# P2P_1.net
KiCad netlist of a schematic drawn in EAGLE
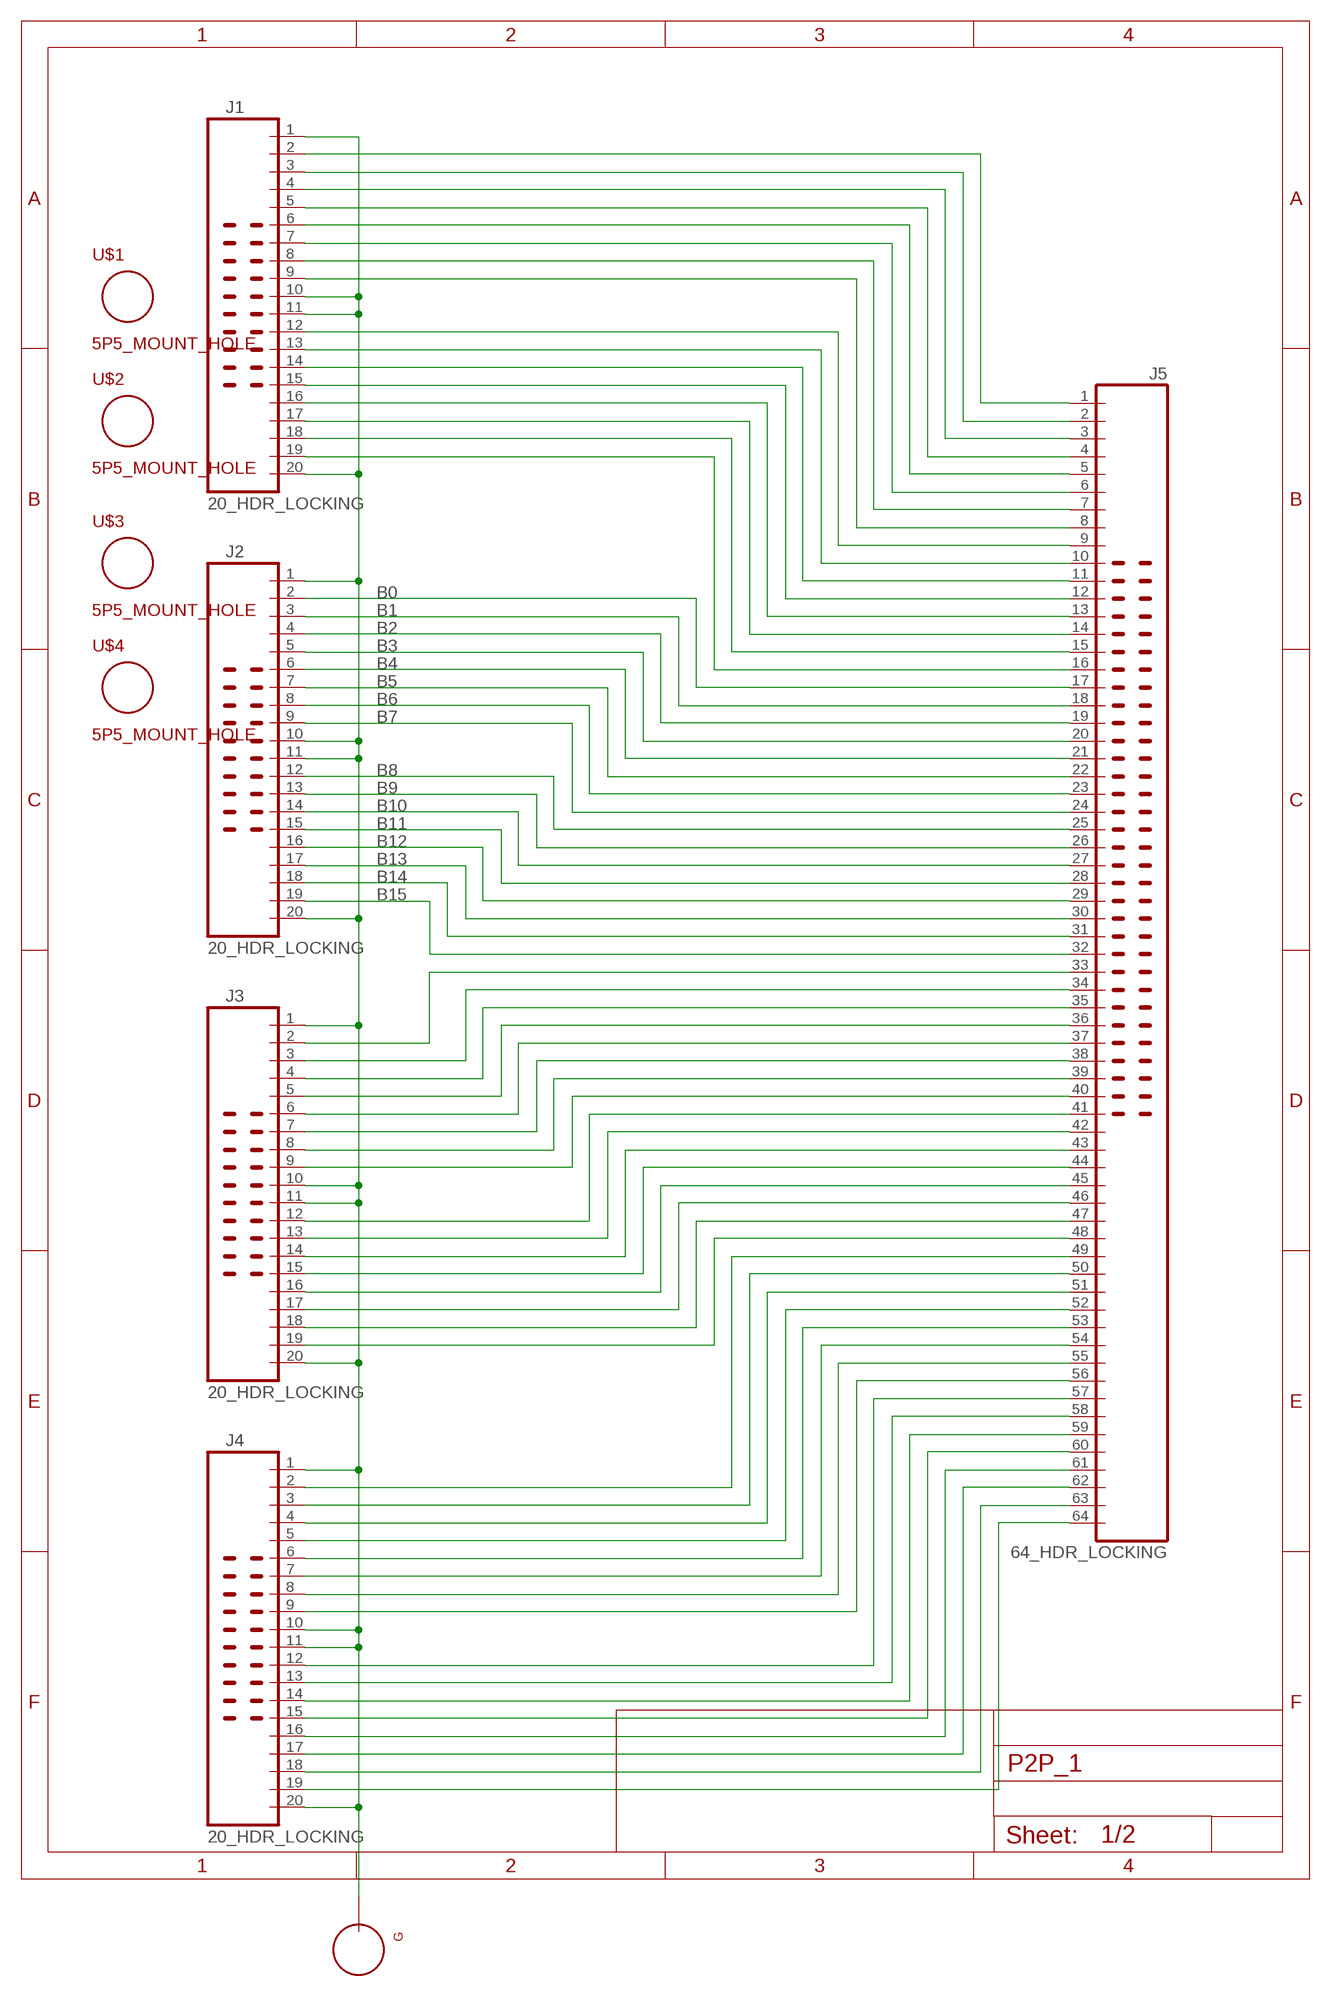
[diagram p0: schematic, sheet 1]
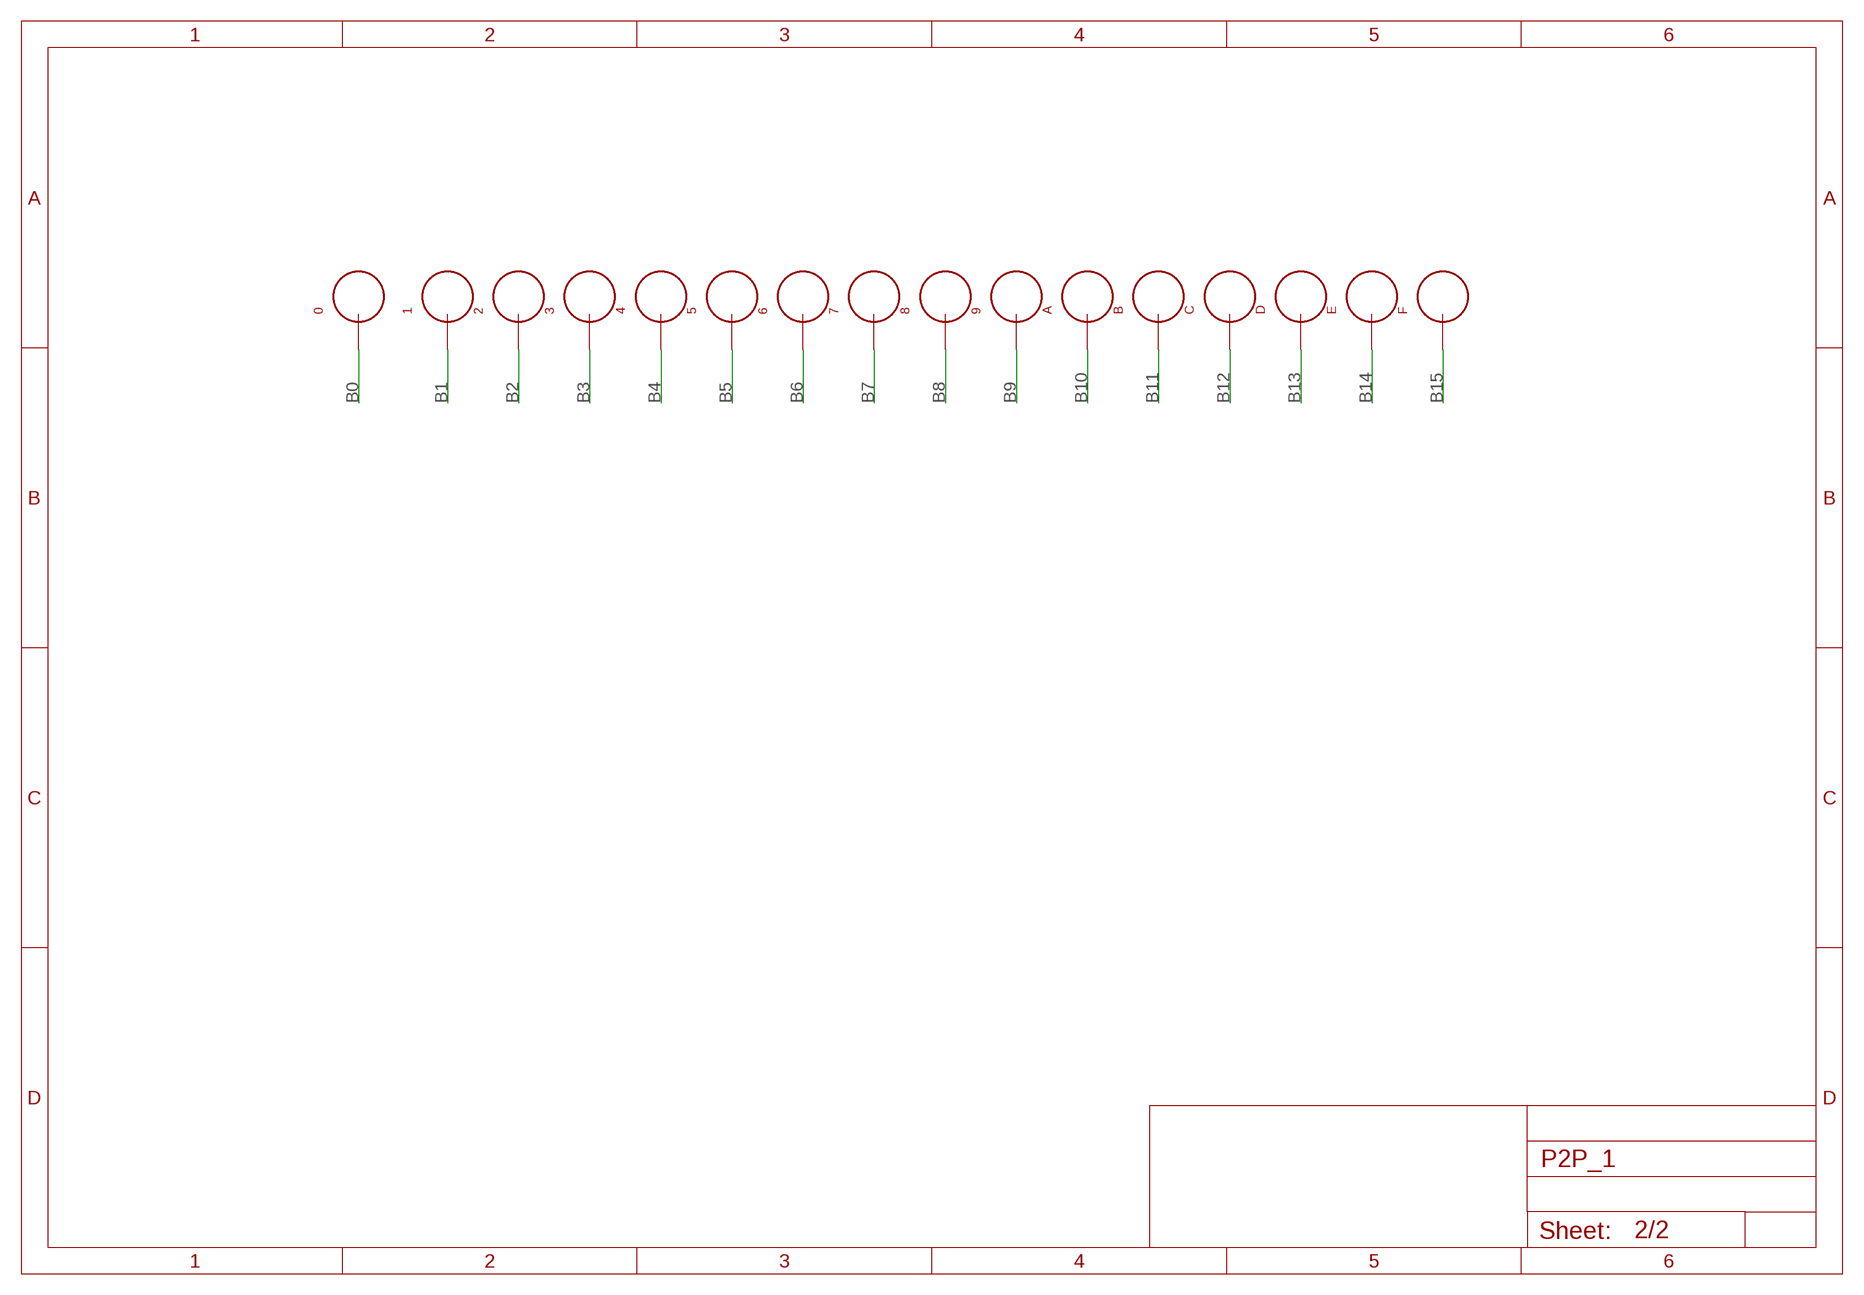
[diagram p1: schematic, sheet 2]

(export (version "E")
  (design (tool "Eeschema 10.0.6"))
  (components
    (comp (ref "G")
      (value "TEST_LOOP")
      (footprint "eagle-import:TEST_LOOP")
      (libsource (lib "eagle-import") (part "TEST_LOOP"))
    )
    (comp (ref "J1")
      (value "20_HDR_LOCKING")
      (footprint "eagle-import:20_HDR_LOCKING")
      (libsource (lib "eagle-import") (part "20_HDR_LOCKING"))
    )
    (comp (ref "J2")
      (value "20_HDR_LOCKING")
      (footprint "eagle-import:20_HDR_LOCKING")
      (libsource (lib "eagle-import") (part "20_HDR_LOCKING"))
    )
    (comp (ref "J3")
      (value "20_HDR_LOCKING")
      (footprint "eagle-import:20_HDR_LOCKING")
      (libsource (lib "eagle-import") (part "20_HDR_LOCKING"))
    )
    (comp (ref "J4")
      (value "20_HDR_LOCKING")
      (footprint "eagle-import:20_HDR_LOCKING")
      (libsource (lib "eagle-import") (part "20_HDR_LOCKING"))
    )
    (comp (ref "J5")
      (value "64_HDR_LOCKING")
      (footprint "eagle-import:64_HDR_LOCKING")
      (libsource (lib "eagle-import") (part "64_HDR_LOCKING"))
    )
    (comp (ref "U$1")
      (value "5P5_MOUNT_HOLE")
      (footprint "eagle-import:5P5M_HOLE")
      (libsource (lib "eagle-import") (part "5P5_MOUNT_HOLE"))
    )
    (comp (ref "U$2")
      (value "5P5_MOUNT_HOLE")
      (footprint "eagle-import:5P5M_HOLE")
      (libsource (lib "eagle-import") (part "5P5_MOUNT_HOLE"))
    )
    (comp (ref "U$3")
      (value "5P5_MOUNT_HOLE")
      (footprint "eagle-import:5P5M_HOLE")
      (libsource (lib "eagle-import") (part "5P5_MOUNT_HOLE"))
    )
    (comp (ref "U$4")
      (value "5P5_MOUNT_HOLE")
      (footprint "eagle-import:5P5M_HOLE")
      (libsource (lib "eagle-import") (part "5P5_MOUNT_HOLE"))
    )
    (comp (ref "0")
      (value "TEST_LOOP")
      (footprint "eagle-import:TEST_LOOP")
      (libsource (lib "eagle-import") (part "TEST_LOOP"))
    )
    (comp (ref "1")
      (value "TEST_LOOP")
      (footprint "eagle-import:TEST_LOOP")
      (libsource (lib "eagle-import") (part "TEST_LOOP"))
    )
    (comp (ref "2")
      (value "TEST_LOOP")
      (footprint "eagle-import:TEST_LOOP")
      (libsource (lib "eagle-import") (part "TEST_LOOP"))
    )
    (comp (ref "3")
      (value "TEST_LOOP")
      (footprint "eagle-import:TEST_LOOP")
      (libsource (lib "eagle-import") (part "TEST_LOOP"))
    )
    (comp (ref "4")
      (value "TEST_LOOP")
      (footprint "eagle-import:TEST_LOOP")
      (libsource (lib "eagle-import") (part "TEST_LOOP"))
    )
    (comp (ref "5")
      (value "TEST_LOOP")
      (footprint "eagle-import:TEST_LOOP")
      (libsource (lib "eagle-import") (part "TEST_LOOP"))
    )
    (comp (ref "6")
      (value "TEST_LOOP")
      (footprint "eagle-import:TEST_LOOP")
      (libsource (lib "eagle-import") (part "TEST_LOOP"))
    )
    (comp (ref "7")
      (value "TEST_LOOP")
      (footprint "eagle-import:TEST_LOOP")
      (libsource (lib "eagle-import") (part "TEST_LOOP"))
    )
    (comp (ref "8")
      (value "TEST_LOOP")
      (footprint "eagle-import:TEST_LOOP")
      (libsource (lib "eagle-import") (part "TEST_LOOP"))
    )
    (comp (ref "9")
      (value "TEST_LOOP")
      (footprint "eagle-import:TEST_LOOP")
      (libsource (lib "eagle-import") (part "TEST_LOOP"))
    )
    (comp (ref "A")
      (value "TEST_LOOP")
      (footprint "eagle-import:TEST_LOOP")
      (libsource (lib "eagle-import") (part "TEST_LOOP"))
    )
    (comp (ref "B")
      (value "TEST_LOOP")
      (footprint "eagle-import:TEST_LOOP")
      (libsource (lib "eagle-import") (part "TEST_LOOP"))
    )
    (comp (ref "C")
      (value "TEST_LOOP")
      (footprint "eagle-import:TEST_LOOP")
      (libsource (lib "eagle-import") (part "TEST_LOOP"))
    )
    (comp (ref "D")
      (value "TEST_LOOP")
      (footprint "eagle-import:TEST_LOOP")
      (libsource (lib "eagle-import") (part "TEST_LOOP"))
    )
    (comp (ref "E")
      (value "TEST_LOOP")
      (footprint "eagle-import:TEST_LOOP")
      (libsource (lib "eagle-import") (part "TEST_LOOP"))
    )
    (comp (ref "F")
      (value "TEST_LOOP")
      (footprint "eagle-import:TEST_LOOP")
      (libsource (lib "eagle-import") (part "TEST_LOOP"))
    )
  )
  (nets
    (net (code "1") (name "B0") (class "Default")
      (node (ref "0") (pin "P$1") (pinfunction "P$1_P$1") (pintype "bidirectional"))
      (node (ref "J2") (pin "2") (pinfunction "2_2") (pintype "bidirectional"))
      (node (ref "J5") (pin "17") (pinfunction "17_17") (pintype "bidirectional"))
    )
    (net (code "2") (name "B1") (class "Default")
      (node (ref "1") (pin "P$1") (pinfunction "P$1_P$1") (pintype "bidirectional"))
      (node (ref "J2") (pin "3") (pinfunction "3_3") (pintype "bidirectional"))
      (node (ref "J5") (pin "18") (pinfunction "18_18") (pintype "bidirectional"))
    )
    (net (code "3") (name "B2") (class "Default")
      (node (ref "2") (pin "P$1") (pinfunction "P$1_P$1") (pintype "bidirectional"))
      (node (ref "J2") (pin "4") (pinfunction "4_4") (pintype "bidirectional"))
      (node (ref "J5") (pin "19") (pinfunction "19_19") (pintype "bidirectional"))
    )
    (net (code "4") (name "B3") (class "Default")
      (node (ref "3") (pin "P$1") (pinfunction "P$1_P$1") (pintype "bidirectional"))
      (node (ref "J2") (pin "5") (pinfunction "5_5") (pintype "bidirectional"))
      (node (ref "J5") (pin "20") (pinfunction "20_20") (pintype "bidirectional"))
    )
    (net (code "5") (name "B4") (class "Default")
      (node (ref "4") (pin "P$1") (pinfunction "P$1_P$1") (pintype "bidirectional"))
      (node (ref "J2") (pin "6") (pinfunction "6_6") (pintype "bidirectional"))
      (node (ref "J5") (pin "21") (pinfunction "21_21") (pintype "bidirectional"))
    )
    (net (code "6") (name "B5") (class "Default")
      (node (ref "5") (pin "P$1") (pinfunction "P$1_P$1") (pintype "bidirectional"))
      (node (ref "J2") (pin "7") (pinfunction "7_7") (pintype "bidirectional"))
      (node (ref "J5") (pin "22") (pinfunction "22_22") (pintype "bidirectional"))
    )
    (net (code "7") (name "B6") (class "Default")
      (node (ref "6") (pin "P$1") (pinfunction "P$1_P$1") (pintype "bidirectional"))
      (node (ref "J2") (pin "8") (pinfunction "8_8") (pintype "bidirectional"))
      (node (ref "J5") (pin "23") (pinfunction "23_23") (pintype "bidirectional"))
    )
    (net (code "8") (name "B7") (class "Default")
      (node (ref "7") (pin "P$1") (pinfunction "P$1_P$1") (pintype "bidirectional"))
      (node (ref "J2") (pin "9") (pinfunction "9_9") (pintype "bidirectional"))
      (node (ref "J5") (pin "24") (pinfunction "24_24") (pintype "bidirectional"))
    )
    (net (code "9") (name "B8") (class "Default")
      (node (ref "8") (pin "P$1") (pinfunction "P$1_P$1") (pintype "bidirectional"))
      (node (ref "J2") (pin "12") (pinfunction "12_12") (pintype "bidirectional"))
      (node (ref "J5") (pin "25") (pinfunction "25_25") (pintype "bidirectional"))
    )
    (net (code "10") (name "B9") (class "Default")
      (node (ref "9") (pin "P$1") (pinfunction "P$1_P$1") (pintype "bidirectional"))
      (node (ref "J2") (pin "13") (pinfunction "13_13") (pintype "bidirectional"))
      (node (ref "J5") (pin "26") (pinfunction "26_26") (pintype "bidirectional"))
    )
    (net (code "11") (name "B10") (class "Default")
      (node (ref "A") (pin "P$1") (pinfunction "P$1_P$1") (pintype "bidirectional"))
      (node (ref "J2") (pin "14") (pinfunction "14_14") (pintype "bidirectional"))
      (node (ref "J5") (pin "27") (pinfunction "27_27") (pintype "bidirectional"))
    )
    (net (code "12") (name "B11") (class "Default")
      (node (ref "B") (pin "P$1") (pinfunction "P$1_P$1") (pintype "bidirectional"))
      (node (ref "J2") (pin "15") (pinfunction "15_15") (pintype "bidirectional"))
      (node (ref "J5") (pin "28") (pinfunction "28_28") (pintype "bidirectional"))
    )
    (net (code "13") (name "B12") (class "Default")
      (node (ref "C") (pin "P$1") (pinfunction "P$1_P$1") (pintype "bidirectional"))
      (node (ref "J2") (pin "16") (pinfunction "16_16") (pintype "bidirectional"))
      (node (ref "J5") (pin "29") (pinfunction "29_29") (pintype "bidirectional"))
    )
    (net (code "14") (name "B13") (class "Default")
      (node (ref "D") (pin "P$1") (pinfunction "P$1_P$1") (pintype "bidirectional"))
      (node (ref "J2") (pin "17") (pinfunction "17_17") (pintype "bidirectional"))
      (node (ref "J5") (pin "30") (pinfunction "30_30") (pintype "bidirectional"))
    )
    (net (code "15") (name "B14") (class "Default")
      (node (ref "E") (pin "P$1") (pinfunction "P$1_P$1") (pintype "bidirectional"))
      (node (ref "J2") (pin "18") (pinfunction "18_18") (pintype "bidirectional"))
      (node (ref "J5") (pin "31") (pinfunction "31_31") (pintype "bidirectional"))
    )
    (net (code "16") (name "B15") (class "Default")
      (node (ref "F") (pin "P$1") (pinfunction "P$1_P$1") (pintype "bidirectional"))
      (node (ref "J2") (pin "19") (pinfunction "19_19") (pintype "bidirectional"))
      (node (ref "J5") (pin "32") (pinfunction "32_32") (pintype "bidirectional"))
    )
    (net (code "17") (name "Net-(G-PadP$1)") (class "Default")
      (node (ref "G") (pin "P$1") (pinfunction "P$1_P$1") (pintype "bidirectional"))
      (node (ref "J1") (pin "1") (pinfunction "1_1") (pintype "bidirectional"))
      (node (ref "J1") (pin "10") (pinfunction "10_10") (pintype "bidirectional"))
      (node (ref "J1") (pin "11") (pinfunction "11_11") (pintype "bidirectional"))
      (node (ref "J1") (pin "20") (pinfunction "20_20") (pintype "bidirectional"))
      (node (ref "J2") (pin "1") (pinfunction "1_1") (pintype "bidirectional"))
      (node (ref "J2") (pin "10") (pinfunction "10_10") (pintype "bidirectional"))
      (node (ref "J2") (pin "11") (pinfunction "11_11") (pintype "bidirectional"))
      (node (ref "J2") (pin "20") (pinfunction "20_20") (pintype "bidirectional"))
      (node (ref "J3") (pin "1") (pinfunction "1_1") (pintype "bidirectional"))
      (node (ref "J3") (pin "10") (pinfunction "10_10") (pintype "bidirectional"))
      (node (ref "J3") (pin "11") (pinfunction "11_11") (pintype "bidirectional"))
      (node (ref "J3") (pin "20") (pinfunction "20_20") (pintype "bidirectional"))
      (node (ref "J4") (pin "1") (pinfunction "1_1") (pintype "bidirectional"))
      (node (ref "J4") (pin "10") (pinfunction "10_10") (pintype "bidirectional"))
      (node (ref "J4") (pin "11") (pinfunction "11_11") (pintype "bidirectional"))
      (node (ref "J4") (pin "20") (pinfunction "20_20") (pintype "bidirectional"))
    )
    (net (code "18") (name "Net-(J1-Pad2)") (class "Default")
      (node (ref "J1") (pin "2") (pinfunction "2_2") (pintype "bidirectional"))
      (node (ref "J5") (pin "1") (pinfunction "1_1") (pintype "bidirectional"))
    )
    (net (code "19") (name "Net-(J1-Pad3)") (class "Default")
      (node (ref "J1") (pin "3") (pinfunction "3_3") (pintype "bidirectional"))
      (node (ref "J5") (pin "2") (pinfunction "2_2") (pintype "bidirectional"))
    )
    (net (code "20") (name "Net-(J1-Pad4)") (class "Default")
      (node (ref "J1") (pin "4") (pinfunction "4_4") (pintype "bidirectional"))
      (node (ref "J5") (pin "3") (pinfunction "3_3") (pintype "bidirectional"))
    )
    (net (code "21") (name "Net-(J1-Pad5)") (class "Default")
      (node (ref "J1") (pin "5") (pinfunction "5_5") (pintype "bidirectional"))
      (node (ref "J5") (pin "4") (pinfunction "4_4") (pintype "bidirectional"))
    )
    (net (code "22") (name "Net-(J1-Pad6)") (class "Default")
      (node (ref "J1") (pin "6") (pinfunction "6_6") (pintype "bidirectional"))
      (node (ref "J5") (pin "5") (pinfunction "5_5") (pintype "bidirectional"))
    )
    (net (code "23") (name "Net-(J1-Pad7)") (class "Default")
      (node (ref "J1") (pin "7") (pinfunction "7_7") (pintype "bidirectional"))
      (node (ref "J5") (pin "6") (pinfunction "6_6") (pintype "bidirectional"))
    )
    (net (code "24") (name "Net-(J1-Pad8)") (class "Default")
      (node (ref "J1") (pin "8") (pinfunction "8_8") (pintype "bidirectional"))
      (node (ref "J5") (pin "7") (pinfunction "7_7") (pintype "bidirectional"))
    )
    (net (code "25") (name "Net-(J1-Pad9)") (class "Default")
      (node (ref "J1") (pin "9") (pinfunction "9_9") (pintype "bidirectional"))
      (node (ref "J5") (pin "8") (pinfunction "8_8") (pintype "bidirectional"))
    )
    (net (code "26") (name "Net-(J1-Pad12)") (class "Default")
      (node (ref "J1") (pin "12") (pinfunction "12_12") (pintype "bidirectional"))
      (node (ref "J5") (pin "9") (pinfunction "9_9") (pintype "bidirectional"))
    )
    (net (code "27") (name "Net-(J1-Pad13)") (class "Default")
      (node (ref "J1") (pin "13") (pinfunction "13_13") (pintype "bidirectional"))
      (node (ref "J5") (pin "10") (pinfunction "10_10") (pintype "bidirectional"))
    )
    (net (code "28") (name "Net-(J1-Pad14)") (class "Default")
      (node (ref "J1") (pin "14") (pinfunction "14_14") (pintype "bidirectional"))
      (node (ref "J5") (pin "11") (pinfunction "11_11") (pintype "bidirectional"))
    )
    (net (code "29") (name "Net-(J1-Pad15)") (class "Default")
      (node (ref "J1") (pin "15") (pinfunction "15_15") (pintype "bidirectional"))
      (node (ref "J5") (pin "12") (pinfunction "12_12") (pintype "bidirectional"))
    )
    (net (code "30") (name "Net-(J1-Pad16)") (class "Default")
      (node (ref "J1") (pin "16") (pinfunction "16_16") (pintype "bidirectional"))
      (node (ref "J5") (pin "13") (pinfunction "13_13") (pintype "bidirectional"))
    )
    (net (code "31") (name "Net-(J1-Pad17)") (class "Default")
      (node (ref "J1") (pin "17") (pinfunction "17_17") (pintype "bidirectional"))
      (node (ref "J5") (pin "14") (pinfunction "14_14") (pintype "bidirectional"))
    )
    (net (code "32") (name "Net-(J1-Pad18)") (class "Default")
      (node (ref "J1") (pin "18") (pinfunction "18_18") (pintype "bidirectional"))
      (node (ref "J5") (pin "15") (pinfunction "15_15") (pintype "bidirectional"))
    )
    (net (code "33") (name "Net-(J1-Pad19)") (class "Default")
      (node (ref "J1") (pin "19") (pinfunction "19_19") (pintype "bidirectional"))
      (node (ref "J5") (pin "16") (pinfunction "16_16") (pintype "bidirectional"))
    )
    (net (code "34") (name "Net-(J3-Pad2)") (class "Default")
      (node (ref "J3") (pin "2") (pinfunction "2_2") (pintype "bidirectional"))
      (node (ref "J5") (pin "33") (pinfunction "33_33") (pintype "bidirectional"))
    )
    (net (code "35") (name "Net-(J3-Pad3)") (class "Default")
      (node (ref "J3") (pin "3") (pinfunction "3_3") (pintype "bidirectional"))
      (node (ref "J5") (pin "34") (pinfunction "34_34") (pintype "bidirectional"))
    )
    (net (code "36") (name "Net-(J3-Pad4)") (class "Default")
      (node (ref "J3") (pin "4") (pinfunction "4_4") (pintype "bidirectional"))
      (node (ref "J5") (pin "35") (pinfunction "35_35") (pintype "bidirectional"))
    )
    (net (code "37") (name "Net-(J3-Pad5)") (class "Default")
      (node (ref "J3") (pin "5") (pinfunction "5_5") (pintype "bidirectional"))
      (node (ref "J5") (pin "36") (pinfunction "36_36") (pintype "bidirectional"))
    )
    (net (code "38") (name "Net-(J3-Pad6)") (class "Default")
      (node (ref "J3") (pin "6") (pinfunction "6_6") (pintype "bidirectional"))
      (node (ref "J5") (pin "37") (pinfunction "37_37") (pintype "bidirectional"))
    )
    (net (code "39") (name "Net-(J3-Pad7)") (class "Default")
      (node (ref "J3") (pin "7") (pinfunction "7_7") (pintype "bidirectional"))
      (node (ref "J5") (pin "38") (pinfunction "38_38") (pintype "bidirectional"))
    )
    (net (code "40") (name "Net-(J3-Pad8)") (class "Default")
      (node (ref "J3") (pin "8") (pinfunction "8_8") (pintype "bidirectional"))
      (node (ref "J5") (pin "39") (pinfunction "39_39") (pintype "bidirectional"))
    )
    (net (code "41") (name "Net-(J3-Pad9)") (class "Default")
      (node (ref "J3") (pin "9") (pinfunction "9_9") (pintype "bidirectional"))
      (node (ref "J5") (pin "40") (pinfunction "40_40") (pintype "bidirectional"))
    )
    (net (code "42") (name "Net-(J3-Pad12)") (class "Default")
      (node (ref "J3") (pin "12") (pinfunction "12_12") (pintype "bidirectional"))
      (node (ref "J5") (pin "41") (pinfunction "41_41") (pintype "bidirectional"))
    )
    (net (code "43") (name "Net-(J3-Pad13)") (class "Default")
      (node (ref "J3") (pin "13") (pinfunction "13_13") (pintype "bidirectional"))
      (node (ref "J5") (pin "42") (pinfunction "42_42") (pintype "bidirectional"))
    )
    (net (code "44") (name "Net-(J3-Pad14)") (class "Default")
      (node (ref "J3") (pin "14") (pinfunction "14_14") (pintype "bidirectional"))
      (node (ref "J5") (pin "43") (pinfunction "43_43") (pintype "bidirectional"))
    )
    (net (code "45") (name "Net-(J3-Pad15)") (class "Default")
      (node (ref "J3") (pin "15") (pinfunction "15_15") (pintype "bidirectional"))
      (node (ref "J5") (pin "44") (pinfunction "44_44") (pintype "bidirectional"))
    )
    (net (code "46") (name "Net-(J3-Pad16)") (class "Default")
      (node (ref "J3") (pin "16") (pinfunction "16_16") (pintype "bidirectional"))
      (node (ref "J5") (pin "45") (pinfunction "45_45") (pintype "bidirectional"))
    )
    (net (code "47") (name "Net-(J3-Pad17)") (class "Default")
      (node (ref "J3") (pin "17") (pinfunction "17_17") (pintype "bidirectional"))
      (node (ref "J5") (pin "46") (pinfunction "46_46") (pintype "bidirectional"))
    )
    (net (code "48") (name "Net-(J3-Pad18)") (class "Default")
      (node (ref "J3") (pin "18") (pinfunction "18_18") (pintype "bidirectional"))
      (node (ref "J5") (pin "47") (pinfunction "47_47") (pintype "bidirectional"))
    )
    (net (code "49") (name "Net-(J3-Pad19)") (class "Default")
      (node (ref "J3") (pin "19") (pinfunction "19_19") (pintype "bidirectional"))
      (node (ref "J5") (pin "48") (pinfunction "48_48") (pintype "bidirectional"))
    )
    (net (code "50") (name "Net-(J4-Pad2)") (class "Default")
      (node (ref "J4") (pin "2") (pinfunction "2_2") (pintype "bidirectional"))
      (node (ref "J5") (pin "49") (pinfunction "49_49") (pintype "bidirectional"))
    )
    (net (code "51") (name "Net-(J4-Pad3)") (class "Default")
      (node (ref "J4") (pin "3") (pinfunction "3_3") (pintype "bidirectional"))
      (node (ref "J5") (pin "50") (pinfunction "50_50") (pintype "bidirectional"))
    )
    (net (code "52") (name "Net-(J4-Pad4)") (class "Default")
      (node (ref "J4") (pin "4") (pinfunction "4_4") (pintype "bidirectional"))
      (node (ref "J5") (pin "51") (pinfunction "51_51") (pintype "bidirectional"))
    )
    (net (code "53") (name "Net-(J4-Pad5)") (class "Default")
      (node (ref "J4") (pin "5") (pinfunction "5_5") (pintype "bidirectional"))
      (node (ref "J5") (pin "52") (pinfunction "52_52") (pintype "bidirectional"))
    )
    (net (code "54") (name "Net-(J4-Pad6)") (class "Default")
      (node (ref "J4") (pin "6") (pinfunction "6_6") (pintype "bidirectional"))
      (node (ref "J5") (pin "53") (pinfunction "53_53") (pintype "bidirectional"))
    )
    (net (code "55") (name "Net-(J4-Pad7)") (class "Default")
      (node (ref "J4") (pin "7") (pinfunction "7_7") (pintype "bidirectional"))
      (node (ref "J5") (pin "54") (pinfunction "54_54") (pintype "bidirectional"))
    )
    (net (code "56") (name "Net-(J4-Pad8)") (class "Default")
      (node (ref "J4") (pin "8") (pinfunction "8_8") (pintype "bidirectional"))
      (node (ref "J5") (pin "55") (pinfunction "55_55") (pintype "bidirectional"))
    )
    (net (code "57") (name "Net-(J4-Pad9)") (class "Default")
      (node (ref "J4") (pin "9") (pinfunction "9_9") (pintype "bidirectional"))
      (node (ref "J5") (pin "56") (pinfunction "56_56") (pintype "bidirectional"))
    )
    (net (code "58") (name "Net-(J4-Pad12)") (class "Default")
      (node (ref "J4") (pin "12") (pinfunction "12_12") (pintype "bidirectional"))
      (node (ref "J5") (pin "57") (pinfunction "57_57") (pintype "bidirectional"))
    )
    (net (code "59") (name "Net-(J4-Pad13)") (class "Default")
      (node (ref "J4") (pin "13") (pinfunction "13_13") (pintype "bidirectional"))
      (node (ref "J5") (pin "58") (pinfunction "58_58") (pintype "bidirectional"))
    )
    (net (code "60") (name "Net-(J4-Pad14)") (class "Default")
      (node (ref "J4") (pin "14") (pinfunction "14_14") (pintype "bidirectional"))
      (node (ref "J5") (pin "59") (pinfunction "59_59") (pintype "bidirectional"))
    )
    (net (code "61") (name "Net-(J4-Pad15)") (class "Default")
      (node (ref "J4") (pin "15") (pinfunction "15_15") (pintype "bidirectional"))
      (node (ref "J5") (pin "60") (pinfunction "60_60") (pintype "bidirectional"))
    )
    (net (code "62") (name "Net-(J4-Pad16)") (class "Default")
      (node (ref "J4") (pin "16") (pinfunction "16_16") (pintype "bidirectional"))
      (node (ref "J5") (pin "61") (pinfunction "61_61") (pintype "bidirectional"))
    )
    (net (code "63") (name "Net-(J4-Pad17)") (class "Default")
      (node (ref "J4") (pin "17") (pinfunction "17_17") (pintype "bidirectional"))
      (node (ref "J5") (pin "62") (pinfunction "62_62") (pintype "bidirectional"))
    )
    (net (code "64") (name "Net-(J4-Pad18)") (class "Default")
      (node (ref "J4") (pin "18") (pinfunction "18_18") (pintype "bidirectional"))
      (node (ref "J5") (pin "63") (pinfunction "63_63") (pintype "bidirectional"))
    )
    (net (code "65") (name "Net-(J4-Pad19)") (class "Default")
      (node (ref "J4") (pin "19") (pinfunction "19_19") (pintype "bidirectional"))
      (node (ref "J5") (pin "64") (pinfunction "64_64") (pintype "bidirectional"))
    )
  )
)
